# AP4BP-Module-CarrierBreakout_rev_a_v2.net
KiCad netlist of a schematic drawn in EAGLE
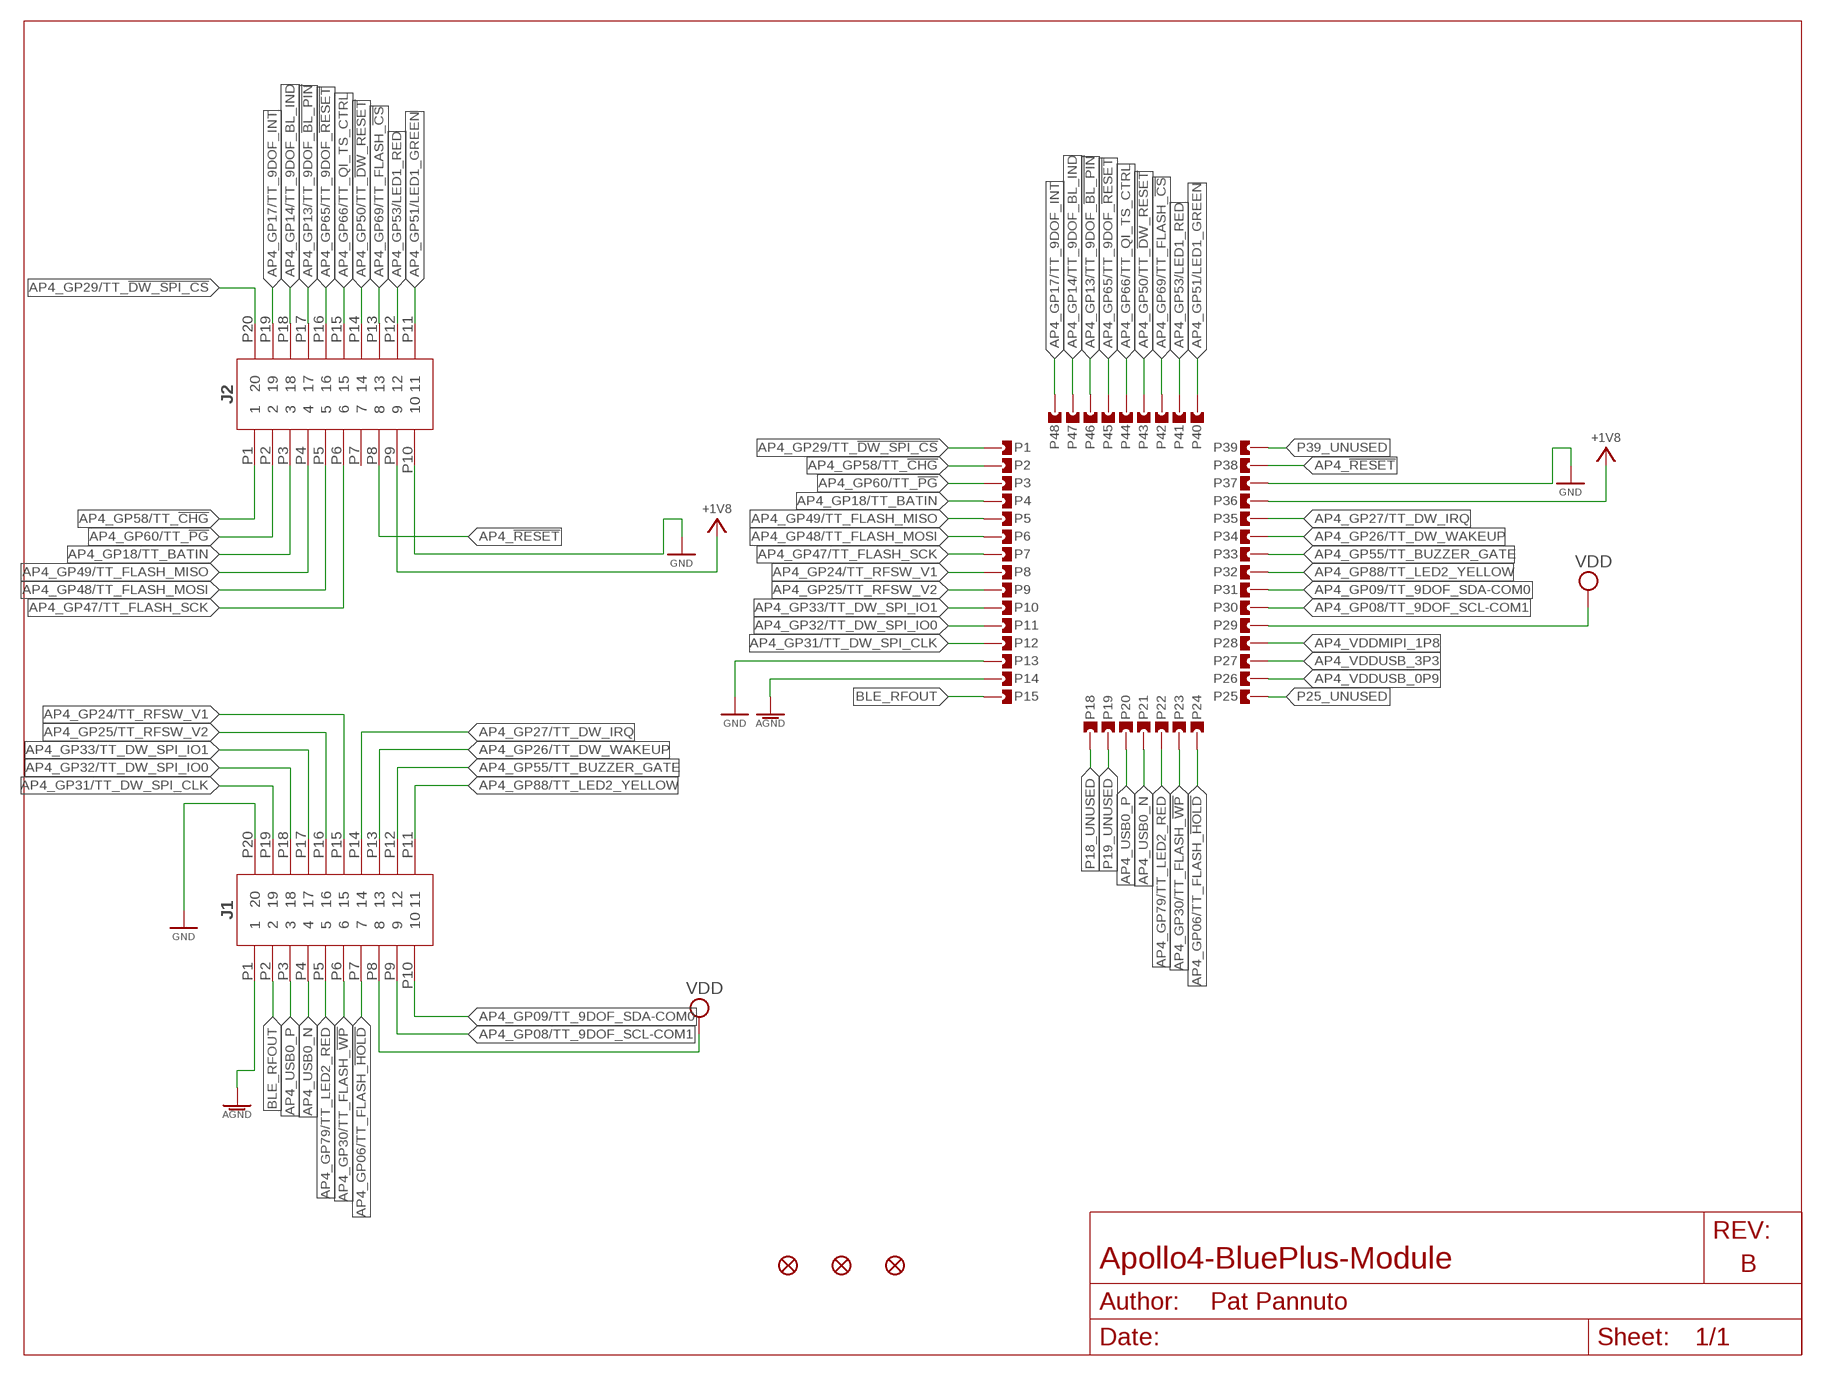
[diagram p0: schematic, sheet 1]

(export (version "E")
  (design (tool "Eeschema 10.0.6"))
  (components
    (comp (ref "FD1")
      (value "FIDUCIALUFIDUCIAL")
      (footprint "eagle-import:FIDUCIAL-MICRO")
      (libsource (lib "eagle-import") (part "FIDUCIALUFIDUCIAL"))
    )
    (comp (ref "FD2")
      (value "FIDUCIALUFIDUCIAL")
      (footprint "eagle-import:FIDUCIAL-MICRO")
      (libsource (lib "eagle-import") (part "FIDUCIALUFIDUCIAL"))
    )
    (comp (ref "FD3")
      (value "FIDUCIALUFIDUCIAL")
      (footprint "eagle-import:FIDUCIAL-MICRO")
      (libsource (lib "eagle-import") (part "FIDUCIALUFIDUCIAL"))
    )
    (comp (ref "J1")
      (value "PINHEAD-SMD-1MM-2X10")
      (footprint "eagle-import:PINHEAD-SMD-1MM-2X10")
      (fields
        (field (name "MANUFACTURER") "TE Connectivity AMP Connectors")
        (field (name "MPN") "1MM-HU-D10-VS-00-H-TBP")
      )
      (libsource (lib "eagle-import") (part "PINHEAD-SMD-1MM-2X10"))
    )
    (comp (ref "J2")
      (value "PINHEAD-SMD-1MM-2X10")
      (footprint "eagle-import:PINHEAD-SMD-1MM-2X10")
      (fields
        (field (name "MANUFACTURER") "TE Connectivity AMP Connectors")
        (field (name "MPN") "1MM-HU-D10-VS-00-H-TBP")
      )
      (libsource (lib "eagle-import") (part "PINHEAD-SMD-1MM-2X10"))
    )
    (comp (ref "P1")
      (value "CASTELLATION4L")
      (footprint "eagle-import:CASTELLATION-0.55MM_DRILL-4L")
      (libsource (lib "eagle-import") (part "CASTELLATION4L"))
    )
    (comp (ref "P2")
      (value "CASTELLATION4L")
      (footprint "eagle-import:CASTELLATION-0.55MM_DRILL-4L")
      (libsource (lib "eagle-import") (part "CASTELLATION4L"))
    )
    (comp (ref "P3")
      (value "CASTELLATION4L")
      (footprint "eagle-import:CASTELLATION-0.55MM_DRILL-4L")
      (libsource (lib "eagle-import") (part "CASTELLATION4L"))
    )
    (comp (ref "P4")
      (value "CASTELLATION4L")
      (footprint "eagle-import:CASTELLATION-0.55MM_DRILL-4L")
      (libsource (lib "eagle-import") (part "CASTELLATION4L"))
    )
    (comp (ref "P5")
      (value "CASTELLATION4L")
      (footprint "eagle-import:CASTELLATION-0.55MM_DRILL-4L")
      (libsource (lib "eagle-import") (part "CASTELLATION4L"))
    )
    (comp (ref "P6")
      (value "CASTELLATION4L")
      (footprint "eagle-import:CASTELLATION-0.55MM_DRILL-4L")
      (libsource (lib "eagle-import") (part "CASTELLATION4L"))
    )
    (comp (ref "P7")
      (value "CASTELLATION4L")
      (footprint "eagle-import:CASTELLATION-0.55MM_DRILL-4L")
      (libsource (lib "eagle-import") (part "CASTELLATION4L"))
    )
    (comp (ref "P8")
      (value "CASTELLATION4L")
      (footprint "eagle-import:CASTELLATION-0.55MM_DRILL-4L")
      (libsource (lib "eagle-import") (part "CASTELLATION4L"))
    )
    (comp (ref "P9")
      (value "CASTELLATION4L")
      (footprint "eagle-import:CASTELLATION-0.55MM_DRILL-4L")
      (libsource (lib "eagle-import") (part "CASTELLATION4L"))
    )
    (comp (ref "P10")
      (value "CASTELLATION4L")
      (footprint "eagle-import:CASTELLATION-0.55MM_DRILL-4L")
      (libsource (lib "eagle-import") (part "CASTELLATION4L"))
    )
    (comp (ref "P11")
      (value "CASTELLATION4L")
      (footprint "eagle-import:CASTELLATION-0.55MM_DRILL-4L")
      (libsource (lib "eagle-import") (part "CASTELLATION4L"))
    )
    (comp (ref "P12")
      (value "CASTELLATION4L")
      (footprint "eagle-import:CASTELLATION-0.55MM_DRILL-4L")
      (libsource (lib "eagle-import") (part "CASTELLATION4L"))
    )
    (comp (ref "P13")
      (value "CASTELLATION4L")
      (footprint "eagle-import:CASTELLATION-0.55MM_DRILL-4L")
      (libsource (lib "eagle-import") (part "CASTELLATION4L"))
    )
    (comp (ref "P14")
      (value "CASTELLATION4L")
      (footprint "eagle-import:CASTELLATION-0.55MM_DRILL-4L")
      (libsource (lib "eagle-import") (part "CASTELLATION4L"))
    )
    (comp (ref "P15")
      (value "CASTELLATION4L")
      (footprint "eagle-import:CASTELLATION-0.55MM_DRILL-4L")
      (libsource (lib "eagle-import") (part "CASTELLATION4L"))
    )
    (comp (ref "P18")
      (value "CASTELLATION4L")
      (footprint "eagle-import:CASTELLATION-0.55MM_DRILL-4L")
      (libsource (lib "eagle-import") (part "CASTELLATION4L"))
    )
    (comp (ref "P19")
      (value "CASTELLATION4L")
      (footprint "eagle-import:CASTELLATION-0.55MM_DRILL-4L")
      (libsource (lib "eagle-import") (part "CASTELLATION4L"))
    )
    (comp (ref "P20")
      (value "CASTELLATION4L")
      (footprint "eagle-import:CASTELLATION-0.55MM_DRILL-4L")
      (libsource (lib "eagle-import") (part "CASTELLATION4L"))
    )
    (comp (ref "P21")
      (value "CASTELLATION4L")
      (footprint "eagle-import:CASTELLATION-0.55MM_DRILL-4L")
      (libsource (lib "eagle-import") (part "CASTELLATION4L"))
    )
    (comp (ref "P22")
      (value "CASTELLATION4L")
      (footprint "eagle-import:CASTELLATION-0.55MM_DRILL-4L")
      (libsource (lib "eagle-import") (part "CASTELLATION4L"))
    )
    (comp (ref "P23")
      (value "CASTELLATION4L")
      (footprint "eagle-import:CASTELLATION-0.55MM_DRILL-4L")
      (libsource (lib "eagle-import") (part "CASTELLATION4L"))
    )
    (comp (ref "P24")
      (value "CASTELLATION4L")
      (footprint "eagle-import:CASTELLATION-0.55MM_DRILL-4L")
      (libsource (lib "eagle-import") (part "CASTELLATION4L"))
    )
    (comp (ref "P25")
      (value "CASTELLATION4L")
      (footprint "eagle-import:CASTELLATION-0.55MM_DRILL-4L")
      (libsource (lib "eagle-import") (part "CASTELLATION4L"))
    )
    (comp (ref "P26")
      (value "CASTELLATION4L")
      (footprint "eagle-import:CASTELLATION-0.55MM_DRILL-4L")
      (libsource (lib "eagle-import") (part "CASTELLATION4L"))
    )
    (comp (ref "P27")
      (value "CASTELLATION4L")
      (footprint "eagle-import:CASTELLATION-0.55MM_DRILL-4L")
      (libsource (lib "eagle-import") (part "CASTELLATION4L"))
    )
    (comp (ref "P28")
      (value "CASTELLATION4L")
      (footprint "eagle-import:CASTELLATION-0.55MM_DRILL-4L")
      (libsource (lib "eagle-import") (part "CASTELLATION4L"))
    )
    (comp (ref "P29")
      (value "CASTELLATION4L")
      (footprint "eagle-import:CASTELLATION-0.55MM_DRILL-4L")
      (libsource (lib "eagle-import") (part "CASTELLATION4L"))
    )
    (comp (ref "P30")
      (value "CASTELLATION4L")
      (footprint "eagle-import:CASTELLATION-0.55MM_DRILL-4L")
      (libsource (lib "eagle-import") (part "CASTELLATION4L"))
    )
    (comp (ref "P31")
      (value "CASTELLATION4L")
      (footprint "eagle-import:CASTELLATION-0.55MM_DRILL-4L")
      (libsource (lib "eagle-import") (part "CASTELLATION4L"))
    )
    (comp (ref "P32")
      (value "CASTELLATION4L")
      (footprint "eagle-import:CASTELLATION-0.55MM_DRILL-4L")
      (libsource (lib "eagle-import") (part "CASTELLATION4L"))
    )
    (comp (ref "P33")
      (value "CASTELLATION4L")
      (footprint "eagle-import:CASTELLATION-0.55MM_DRILL-4L")
      (libsource (lib "eagle-import") (part "CASTELLATION4L"))
    )
    (comp (ref "P34")
      (value "CASTELLATION4L")
      (footprint "eagle-import:CASTELLATION-0.55MM_DRILL-4L")
      (libsource (lib "eagle-import") (part "CASTELLATION4L"))
    )
    (comp (ref "P35")
      (value "CASTELLATION4L")
      (footprint "eagle-import:CASTELLATION-0.55MM_DRILL-4L")
      (libsource (lib "eagle-import") (part "CASTELLATION4L"))
    )
    (comp (ref "P36")
      (value "CASTELLATION4L")
      (footprint "eagle-import:CASTELLATION-0.55MM_DRILL-4L")
      (libsource (lib "eagle-import") (part "CASTELLATION4L"))
    )
    (comp (ref "P37")
      (value "CASTELLATION4L")
      (footprint "eagle-import:CASTELLATION-0.55MM_DRILL-4L")
      (libsource (lib "eagle-import") (part "CASTELLATION4L"))
    )
    (comp (ref "P38")
      (value "CASTELLATION4L")
      (footprint "eagle-import:CASTELLATION-0.55MM_DRILL-4L")
      (libsource (lib "eagle-import") (part "CASTELLATION4L"))
    )
    (comp (ref "P39")
      (value "CASTELLATION4L")
      (footprint "eagle-import:CASTELLATION-0.55MM_DRILL-4L")
      (libsource (lib "eagle-import") (part "CASTELLATION4L"))
    )
    (comp (ref "P40")
      (value "CASTELLATION4L")
      (footprint "eagle-import:CASTELLATION-0.55MM_DRILL-4L")
      (libsource (lib "eagle-import") (part "CASTELLATION4L"))
    )
    (comp (ref "P41")
      (value "CASTELLATION4L")
      (footprint "eagle-import:CASTELLATION-0.55MM_DRILL-4L")
      (libsource (lib "eagle-import") (part "CASTELLATION4L"))
    )
    (comp (ref "P42")
      (value "CASTELLATION4L")
      (footprint "eagle-import:CASTELLATION-0.55MM_DRILL-4L")
      (libsource (lib "eagle-import") (part "CASTELLATION4L"))
    )
    (comp (ref "P43")
      (value "CASTELLATION4L")
      (footprint "eagle-import:CASTELLATION-0.55MM_DRILL-4L")
      (libsource (lib "eagle-import") (part "CASTELLATION4L"))
    )
    (comp (ref "P44")
      (value "CASTELLATION4L")
      (footprint "eagle-import:CASTELLATION-0.55MM_DRILL-4L")
      (libsource (lib "eagle-import") (part "CASTELLATION4L"))
    )
    (comp (ref "P45")
      (value "CASTELLATION4L")
      (footprint "eagle-import:CASTELLATION-0.55MM_DRILL-4L")
      (libsource (lib "eagle-import") (part "CASTELLATION4L"))
    )
    (comp (ref "P46")
      (value "CASTELLATION4L")
      (footprint "eagle-import:CASTELLATION-0.55MM_DRILL-4L")
      (libsource (lib "eagle-import") (part "CASTELLATION4L"))
    )
    (comp (ref "P47")
      (value "CASTELLATION4L")
      (footprint "eagle-import:CASTELLATION-0.55MM_DRILL-4L")
      (libsource (lib "eagle-import") (part "CASTELLATION4L"))
    )
    (comp (ref "P48")
      (value "CASTELLATION4L")
      (footprint "eagle-import:CASTELLATION-0.55MM_DRILL-4L")
      (libsource (lib "eagle-import") (part "CASTELLATION4L"))
    )
  )
  (nets
    (net (code "1") (name "+1V8") (class "Default")
      (node (ref "J2") (pin "P9") (pinfunction "9_P9") (pintype "bidirectional"))
      (node (ref "P36") (pin "P$1") (pinfunction "P$1_P$1") (pintype "bidirectional"))
      (node (ref "P36") (pin "P$2") (pinfunction "P$1_P$2") (pintype "bidirectional"))
      (node (ref "P36") (pin "P$3") (pinfunction "P$1_P$3") (pintype "bidirectional"))
    )
    (net (code "2") (name "/AP4_GP06{slash}TT_FLASH_~{HOLD}") (class "Default")
      (node (ref "J1") (pin "P7") (pinfunction "7_P7") (pintype "bidirectional"))
      (node (ref "P24") (pin "P$1") (pinfunction "P$1_P$1") (pintype "bidirectional"))
      (node (ref "P24") (pin "P$2") (pinfunction "P$1_P$2") (pintype "bidirectional"))
      (node (ref "P24") (pin "P$3") (pinfunction "P$1_P$3") (pintype "bidirectional"))
    )
    (net (code "3") (name "/AP4_GP13{slash}TT_9DOF_~{BL_PIN}") (class "Default")
      (node (ref "J2") (pin "P17") (pinfunction "17_P17") (pintype "bidirectional"))
      (node (ref "P46") (pin "P$1") (pinfunction "P$1_P$1") (pintype "bidirectional"))
      (node (ref "P46") (pin "P$2") (pinfunction "P$1_P$2") (pintype "bidirectional"))
      (node (ref "P46") (pin "P$3") (pinfunction "P$1_P$3") (pintype "bidirectional"))
    )
    (net (code "4") (name "/AP4_GP29{slash}TT_~{DW_SPI_CS}") (class "Default")
      (node (ref "J2") (pin "P20") (pinfunction "20_P20") (pintype "bidirectional"))
      (node (ref "P1") (pin "P$1") (pinfunction "P$1_P$1") (pintype "bidirectional"))
      (node (ref "P1") (pin "P$2") (pinfunction "P$1_P$2") (pintype "bidirectional"))
      (node (ref "P1") (pin "P$3") (pinfunction "P$1_P$3") (pintype "bidirectional"))
    )
    (net (code "5") (name "/AP4_GP30{slash}TT_FLASH_~{WP}") (class "Default")
      (node (ref "J1") (pin "P6") (pinfunction "6_P6") (pintype "bidirectional"))
      (node (ref "P23") (pin "P$1") (pinfunction "P$1_P$1") (pintype "bidirectional"))
      (node (ref "P23") (pin "P$2") (pinfunction "P$1_P$2") (pintype "bidirectional"))
      (node (ref "P23") (pin "P$3") (pinfunction "P$1_P$3") (pintype "bidirectional"))
    )
    (net (code "6") (name "/AP4_GP50{slash}TT_~{DW_RESET}") (class "Default")
      (node (ref "J2") (pin "P14") (pinfunction "14_P14") (pintype "bidirectional"))
      (node (ref "P43") (pin "P$1") (pinfunction "P$1_P$1") (pintype "bidirectional"))
      (node (ref "P43") (pin "P$2") (pinfunction "P$1_P$2") (pintype "bidirectional"))
      (node (ref "P43") (pin "P$3") (pinfunction "P$1_P$3") (pintype "bidirectional"))
    )
    (net (code "7") (name "/AP4_GP58{slash}TT_~{CHG}") (class "Default")
      (node (ref "J2") (pin "P1") (pinfunction "1_P1") (pintype "bidirectional"))
      (node (ref "P2") (pin "P$1") (pinfunction "P$1_P$1") (pintype "bidirectional"))
      (node (ref "P2") (pin "P$2") (pinfunction "P$1_P$2") (pintype "bidirectional"))
      (node (ref "P2") (pin "P$3") (pinfunction "P$1_P$3") (pintype "bidirectional"))
    )
    (net (code "8") (name "/AP4_GP60{slash}TT_~{PG}") (class "Default")
      (node (ref "J2") (pin "P2") (pinfunction "2_P2") (pintype "bidirectional"))
      (node (ref "P3") (pin "P$1") (pinfunction "P$1_P$1") (pintype "bidirectional"))
      (node (ref "P3") (pin "P$2") (pinfunction "P$1_P$2") (pintype "bidirectional"))
      (node (ref "P3") (pin "P$3") (pinfunction "P$1_P$3") (pintype "bidirectional"))
    )
    (net (code "9") (name "/AP4_GP65{slash}TT_9DOF_~{RESET}") (class "Default")
      (node (ref "J2") (pin "P16") (pinfunction "16_P16") (pintype "bidirectional"))
      (node (ref "P45") (pin "P$1") (pinfunction "P$1_P$1") (pintype "bidirectional"))
      (node (ref "P45") (pin "P$2") (pinfunction "P$1_P$2") (pintype "bidirectional"))
      (node (ref "P45") (pin "P$3") (pinfunction "P$1_P$3") (pintype "bidirectional"))
    )
    (net (code "10") (name "/AP4_GP69{slash}TT_FLASH_~{CS}") (class "Default")
      (node (ref "J2") (pin "P13") (pinfunction "13_P13") (pintype "bidirectional"))
      (node (ref "P42") (pin "P$1") (pinfunction "P$1_P$1") (pintype "bidirectional"))
      (node (ref "P42") (pin "P$2") (pinfunction "P$1_P$2") (pintype "bidirectional"))
      (node (ref "P42") (pin "P$3") (pinfunction "P$1_P$3") (pintype "bidirectional"))
    )
    (net (code "11") (name "/AP4_~{RESET}") (class "Default")
      (node (ref "J2") (pin "P8") (pinfunction "8_P8") (pintype "bidirectional"))
      (node (ref "P38") (pin "P$1") (pinfunction "P$1_P$1") (pintype "bidirectional"))
      (node (ref "P38") (pin "P$2") (pinfunction "P$1_P$2") (pintype "bidirectional"))
      (node (ref "P38") (pin "P$3") (pinfunction "P$1_P$3") (pintype "bidirectional"))
    )
    (net (code "12") (name "AGND") (class "Default")
      (node (ref "J1") (pin "P1") (pinfunction "1_P1") (pintype "bidirectional"))
      (node (ref "P14") (pin "P$1") (pinfunction "P$1_P$1") (pintype "bidirectional"))
      (node (ref "P14") (pin "P$2") (pinfunction "P$1_P$2") (pintype "bidirectional"))
      (node (ref "P14") (pin "P$3") (pinfunction "P$1_P$3") (pintype "bidirectional"))
    )
    (net (code "13") (name "AP4_GP08{slash}TT_9DOF_SCL-COM1") (class "Default")
      (node (ref "J1") (pin "P9") (pinfunction "9_P9") (pintype "bidirectional"))
      (node (ref "P30") (pin "P$1") (pinfunction "P$1_P$1") (pintype "bidirectional"))
      (node (ref "P30") (pin "P$2") (pinfunction "P$1_P$2") (pintype "bidirectional"))
      (node (ref "P30") (pin "P$3") (pinfunction "P$1_P$3") (pintype "bidirectional"))
    )
    (net (code "14") (name "AP4_GP09{slash}TT_9DOF_SDA-COM0") (class "Default")
      (node (ref "J1") (pin "P10") (pinfunction "10_P10") (pintype "bidirectional"))
      (node (ref "P31") (pin "P$1") (pinfunction "P$1_P$1") (pintype "bidirectional"))
      (node (ref "P31") (pin "P$2") (pinfunction "P$1_P$2") (pintype "bidirectional"))
      (node (ref "P31") (pin "P$3") (pinfunction "P$1_P$3") (pintype "bidirectional"))
    )
    (net (code "15") (name "AP4_GP14{slash}TT_9DOF_BL_IND") (class "Default")
      (node (ref "J2") (pin "P18") (pinfunction "18_P18") (pintype "bidirectional"))
      (node (ref "P47") (pin "P$1") (pinfunction "P$1_P$1") (pintype "bidirectional"))
      (node (ref "P47") (pin "P$2") (pinfunction "P$1_P$2") (pintype "bidirectional"))
      (node (ref "P47") (pin "P$3") (pinfunction "P$1_P$3") (pintype "bidirectional"))
    )
    (net (code "16") (name "AP4_GP17{slash}TT_9DOF_INT") (class "Default")
      (node (ref "J2") (pin "P19") (pinfunction "19_P19") (pintype "bidirectional"))
      (node (ref "P48") (pin "P$1") (pinfunction "P$1_P$1") (pintype "bidirectional"))
      (node (ref "P48") (pin "P$2") (pinfunction "P$1_P$2") (pintype "bidirectional"))
      (node (ref "P48") (pin "P$3") (pinfunction "P$1_P$3") (pintype "bidirectional"))
    )
    (net (code "17") (name "AP4_GP18{slash}TT_BATIN") (class "Default")
      (node (ref "J2") (pin "P3") (pinfunction "3_P3") (pintype "bidirectional"))
      (node (ref "P4") (pin "P$1") (pinfunction "P$1_P$1") (pintype "bidirectional"))
      (node (ref "P4") (pin "P$2") (pinfunction "P$1_P$2") (pintype "bidirectional"))
      (node (ref "P4") (pin "P$3") (pinfunction "P$1_P$3") (pintype "bidirectional"))
    )
    (net (code "18") (name "AP4_GP24{slash}TT_RFSW_V1") (class "Default")
      (node (ref "J1") (pin "P15") (pinfunction "15_P15") (pintype "bidirectional"))
      (node (ref "P8") (pin "P$1") (pinfunction "P$1_P$1") (pintype "bidirectional"))
      (node (ref "P8") (pin "P$2") (pinfunction "P$1_P$2") (pintype "bidirectional"))
      (node (ref "P8") (pin "P$3") (pinfunction "P$1_P$3") (pintype "bidirectional"))
    )
    (net (code "19") (name "AP4_GP25{slash}TT_RFSW_V2") (class "Default")
      (node (ref "J1") (pin "P16") (pinfunction "16_P16") (pintype "bidirectional"))
      (node (ref "P9") (pin "P$1") (pinfunction "P$1_P$1") (pintype "bidirectional"))
      (node (ref "P9") (pin "P$2") (pinfunction "P$1_P$2") (pintype "bidirectional"))
      (node (ref "P9") (pin "P$3") (pinfunction "P$1_P$3") (pintype "bidirectional"))
    )
    (net (code "20") (name "AP4_GP26{slash}TT_DW_WAKEUP") (class "Default")
      (node (ref "J1") (pin "P13") (pinfunction "13_P13") (pintype "bidirectional"))
      (node (ref "P34") (pin "P$1") (pinfunction "P$1_P$1") (pintype "bidirectional"))
      (node (ref "P34") (pin "P$2") (pinfunction "P$1_P$2") (pintype "bidirectional"))
      (node (ref "P34") (pin "P$3") (pinfunction "P$1_P$3") (pintype "bidirectional"))
    )
    (net (code "21") (name "AP4_GP27{slash}TT_DW_IRQ") (class "Default")
      (node (ref "J1") (pin "P14") (pinfunction "14_P14") (pintype "bidirectional"))
      (node (ref "P35") (pin "P$1") (pinfunction "P$1_P$1") (pintype "bidirectional"))
      (node (ref "P35") (pin "P$2") (pinfunction "P$1_P$2") (pintype "bidirectional"))
      (node (ref "P35") (pin "P$3") (pinfunction "P$1_P$3") (pintype "bidirectional"))
    )
    (net (code "22") (name "AP4_GP31{slash}TT_DW_SPI_CLK") (class "Default")
      (node (ref "J1") (pin "P19") (pinfunction "19_P19") (pintype "bidirectional"))
      (node (ref "P12") (pin "P$1") (pinfunction "P$1_P$1") (pintype "bidirectional"))
      (node (ref "P12") (pin "P$2") (pinfunction "P$1_P$2") (pintype "bidirectional"))
      (node (ref "P12") (pin "P$3") (pinfunction "P$1_P$3") (pintype "bidirectional"))
    )
    (net (code "23") (name "AP4_GP32{slash}TT_DW_SPI_IO0") (class "Default")
      (node (ref "J1") (pin "P18") (pinfunction "18_P18") (pintype "bidirectional"))
      (node (ref "P11") (pin "P$1") (pinfunction "P$1_P$1") (pintype "bidirectional"))
      (node (ref "P11") (pin "P$2") (pinfunction "P$1_P$2") (pintype "bidirectional"))
      (node (ref "P11") (pin "P$3") (pinfunction "P$1_P$3") (pintype "bidirectional"))
    )
    (net (code "24") (name "AP4_GP33{slash}TT_DW_SPI_IO1") (class "Default")
      (node (ref "J1") (pin "P17") (pinfunction "17_P17") (pintype "bidirectional"))
      (node (ref "P10") (pin "P$1") (pinfunction "P$1_P$1") (pintype "bidirectional"))
      (node (ref "P10") (pin "P$2") (pinfunction "P$1_P$2") (pintype "bidirectional"))
      (node (ref "P10") (pin "P$3") (pinfunction "P$1_P$3") (pintype "bidirectional"))
    )
    (net (code "25") (name "AP4_GP47{slash}TT_FLASH_SCK") (class "Default")
      (node (ref "J2") (pin "P6") (pinfunction "6_P6") (pintype "bidirectional"))
      (node (ref "P7") (pin "P$1") (pinfunction "P$1_P$1") (pintype "bidirectional"))
      (node (ref "P7") (pin "P$2") (pinfunction "P$1_P$2") (pintype "bidirectional"))
      (node (ref "P7") (pin "P$3") (pinfunction "P$1_P$3") (pintype "bidirectional"))
    )
    (net (code "26") (name "AP4_GP48{slash}TT_FLASH_MOSI") (class "Default")
      (node (ref "J2") (pin "P5") (pinfunction "5_P5") (pintype "bidirectional"))
      (node (ref "P6") (pin "P$1") (pinfunction "P$1_P$1") (pintype "bidirectional"))
      (node (ref "P6") (pin "P$2") (pinfunction "P$1_P$2") (pintype "bidirectional"))
      (node (ref "P6") (pin "P$3") (pinfunction "P$1_P$3") (pintype "bidirectional"))
    )
    (net (code "27") (name "AP4_GP49{slash}TT_FLASH_MISO") (class "Default")
      (node (ref "J2") (pin "P4") (pinfunction "4_P4") (pintype "bidirectional"))
      (node (ref "P5") (pin "P$1") (pinfunction "P$1_P$1") (pintype "bidirectional"))
      (node (ref "P5") (pin "P$2") (pinfunction "P$1_P$2") (pintype "bidirectional"))
      (node (ref "P5") (pin "P$3") (pinfunction "P$1_P$3") (pintype "bidirectional"))
    )
    (net (code "28") (name "AP4_GP51{slash}LED1_GREEN") (class "Default")
      (node (ref "J2") (pin "P11") (pinfunction "11_P11") (pintype "bidirectional"))
      (node (ref "P40") (pin "P$1") (pinfunction "P$1_P$1") (pintype "bidirectional"))
      (node (ref "P40") (pin "P$2") (pinfunction "P$1_P$2") (pintype "bidirectional"))
      (node (ref "P40") (pin "P$3") (pinfunction "P$1_P$3") (pintype "bidirectional"))
    )
    (net (code "29") (name "AP4_GP53{slash}LED1_RED") (class "Default")
      (node (ref "J2") (pin "P12") (pinfunction "12_P12") (pintype "bidirectional"))
      (node (ref "P41") (pin "P$1") (pinfunction "P$1_P$1") (pintype "bidirectional"))
      (node (ref "P41") (pin "P$2") (pinfunction "P$1_P$2") (pintype "bidirectional"))
      (node (ref "P41") (pin "P$3") (pinfunction "P$1_P$3") (pintype "bidirectional"))
    )
    (net (code "30") (name "AP4_GP55{slash}TT_BUZZER_GATE") (class "Default")
      (node (ref "J1") (pin "P12") (pinfunction "12_P12") (pintype "bidirectional"))
      (node (ref "P33") (pin "P$1") (pinfunction "P$1_P$1") (pintype "bidirectional"))
      (node (ref "P33") (pin "P$2") (pinfunction "P$1_P$2") (pintype "bidirectional"))
      (node (ref "P33") (pin "P$3") (pinfunction "P$1_P$3") (pintype "bidirectional"))
    )
    (net (code "31") (name "AP4_GP66{slash}TT_QI_TS_CTRL") (class "Default")
      (node (ref "J2") (pin "P15") (pinfunction "15_P15") (pintype "bidirectional"))
      (node (ref "P44") (pin "P$1") (pinfunction "P$1_P$1") (pintype "bidirectional"))
      (node (ref "P44") (pin "P$2") (pinfunction "P$1_P$2") (pintype "bidirectional"))
      (node (ref "P44") (pin "P$3") (pinfunction "P$1_P$3") (pintype "bidirectional"))
    )
    (net (code "32") (name "AP4_GP79{slash}TT_LED2_RED") (class "Default")
      (node (ref "J1") (pin "P5") (pinfunction "5_P5") (pintype "bidirectional"))
      (node (ref "P22") (pin "P$1") (pinfunction "P$1_P$1") (pintype "bidirectional"))
      (node (ref "P22") (pin "P$2") (pinfunction "P$1_P$2") (pintype "bidirectional"))
      (node (ref "P22") (pin "P$3") (pinfunction "P$1_P$3") (pintype "bidirectional"))
    )
    (net (code "33") (name "AP4_GP88{slash}TT_LED2_YELLOW") (class "Default")
      (node (ref "J1") (pin "P11") (pinfunction "11_P11") (pintype "bidirectional"))
      (node (ref "P32") (pin "P$1") (pinfunction "P$1_P$1") (pintype "bidirectional"))
      (node (ref "P32") (pin "P$2") (pinfunction "P$1_P$2") (pintype "bidirectional"))
      (node (ref "P32") (pin "P$3") (pinfunction "P$1_P$3") (pintype "bidirectional"))
    )
    (net (code "34") (name "AP4_USB0_N") (class "Default")
      (node (ref "J1") (pin "P4") (pinfunction "4_P4") (pintype "bidirectional"))
      (node (ref "P21") (pin "P$1") (pinfunction "P$1_P$1") (pintype "bidirectional"))
      (node (ref "P21") (pin "P$2") (pinfunction "P$1_P$2") (pintype "bidirectional"))
      (node (ref "P21") (pin "P$3") (pinfunction "P$1_P$3") (pintype "bidirectional"))
    )
    (net (code "35") (name "AP4_USB0_P") (class "Default")
      (node (ref "J1") (pin "P3") (pinfunction "3_P3") (pintype "bidirectional"))
      (node (ref "P20") (pin "P$1") (pinfunction "P$1_P$1") (pintype "bidirectional"))
      (node (ref "P20") (pin "P$2") (pinfunction "P$1_P$2") (pintype "bidirectional"))
      (node (ref "P20") (pin "P$3") (pinfunction "P$1_P$3") (pintype "bidirectional"))
    )
    (net (code "36") (name "AP4_VDDMIPI_1P8") (class "Default")
      (node (ref "P28") (pin "P$1") (pinfunction "P$1_P$1") (pintype "bidirectional"))
      (node (ref "P28") (pin "P$2") (pinfunction "P$1_P$2") (pintype "bidirectional"))
      (node (ref "P28") (pin "P$3") (pinfunction "P$1_P$3") (pintype "bidirectional"))
    )
    (net (code "37") (name "AP4_VDDUSB_0P9") (class "Default")
      (node (ref "P26") (pin "P$1") (pinfunction "P$1_P$1") (pintype "bidirectional"))
      (node (ref "P26") (pin "P$2") (pinfunction "P$1_P$2") (pintype "bidirectional"))
      (node (ref "P26") (pin "P$3") (pinfunction "P$1_P$3") (pintype "bidirectional"))
    )
    (net (code "38") (name "AP4_VDDUSB_3P3") (class "Default")
      (node (ref "P27") (pin "P$1") (pinfunction "P$1_P$1") (pintype "bidirectional"))
      (node (ref "P27") (pin "P$2") (pinfunction "P$1_P$2") (pintype "bidirectional"))
      (node (ref "P27") (pin "P$3") (pinfunction "P$1_P$3") (pintype "bidirectional"))
    )
    (net (code "39") (name "BLE_RFOUT") (class "Default")
      (node (ref "J1") (pin "P2") (pinfunction "2_P2") (pintype "bidirectional"))
      (node (ref "P15") (pin "P$1") (pinfunction "P$1_P$1") (pintype "bidirectional"))
      (node (ref "P15") (pin "P$2") (pinfunction "P$1_P$2") (pintype "bidirectional"))
      (node (ref "P15") (pin "P$3") (pinfunction "P$1_P$3") (pintype "bidirectional"))
    )
    (net (code "40") (name "GND") (class "Default")
      (node (ref "J1") (pin "P20") (pinfunction "20_P20") (pintype "bidirectional"))
      (node (ref "J2") (pin "P10") (pinfunction "10_P10") (pintype "bidirectional"))
      (node (ref "P13") (pin "P$1") (pinfunction "P$1_P$1") (pintype "bidirectional"))
      (node (ref "P13") (pin "P$2") (pinfunction "P$1_P$2") (pintype "bidirectional"))
      (node (ref "P13") (pin "P$3") (pinfunction "P$1_P$3") (pintype "bidirectional"))
      (node (ref "P37") (pin "P$1") (pinfunction "P$1_P$1") (pintype "bidirectional"))
      (node (ref "P37") (pin "P$2") (pinfunction "P$1_P$2") (pintype "bidirectional"))
      (node (ref "P37") (pin "P$3") (pinfunction "P$1_P$3") (pintype "bidirectional"))
    )
    (net (code "41") (name "P18_UNUSED") (class "Default")
      (node (ref "P18") (pin "P$1") (pinfunction "P$1_P$1") (pintype "bidirectional"))
      (node (ref "P18") (pin "P$2") (pinfunction "P$1_P$2") (pintype "bidirectional"))
      (node (ref "P18") (pin "P$3") (pinfunction "P$1_P$3") (pintype "bidirectional"))
    )
    (net (code "42") (name "P19_UNUSED") (class "Default")
      (node (ref "P19") (pin "P$1") (pinfunction "P$1_P$1") (pintype "bidirectional"))
      (node (ref "P19") (pin "P$2") (pinfunction "P$1_P$2") (pintype "bidirectional"))
      (node (ref "P19") (pin "P$3") (pinfunction "P$1_P$3") (pintype "bidirectional"))
    )
    (net (code "43") (name "P25_UNUSED") (class "Default")
      (node (ref "P25") (pin "P$1") (pinfunction "P$1_P$1") (pintype "bidirectional"))
      (node (ref "P25") (pin "P$2") (pinfunction "P$1_P$2") (pintype "bidirectional"))
      (node (ref "P25") (pin "P$3") (pinfunction "P$1_P$3") (pintype "bidirectional"))
    )
    (net (code "44") (name "P39_UNUSED") (class "Default")
      (node (ref "P39") (pin "P$1") (pinfunction "P$1_P$1") (pintype "bidirectional"))
      (node (ref "P39") (pin "P$2") (pinfunction "P$1_P$2") (pintype "bidirectional"))
      (node (ref "P39") (pin "P$3") (pinfunction "P$1_P$3") (pintype "bidirectional"))
    )
    (net (code "45") (name "VDD") (class "Default")
      (node (ref "J1") (pin "P8") (pinfunction "8_P8") (pintype "bidirectional"))
      (node (ref "P29") (pin "P$1") (pinfunction "P$1_P$1") (pintype "bidirectional"))
      (node (ref "P29") (pin "P$2") (pinfunction "P$1_P$2") (pintype "bidirectional"))
      (node (ref "P29") (pin "P$3") (pinfunction "P$1_P$3") (pintype "bidirectional"))
    )
    (net (code "46") (name "unconnected-(J2-7-PadP7)") (class "Default")
      (node (ref "J2") (pin "P7") (pinfunction "7_P7") (pintype "bidirectional"))
    )
  )
)
